# fmc_connector.net
KiCad netlist of a schematic drawn in Altium Designer
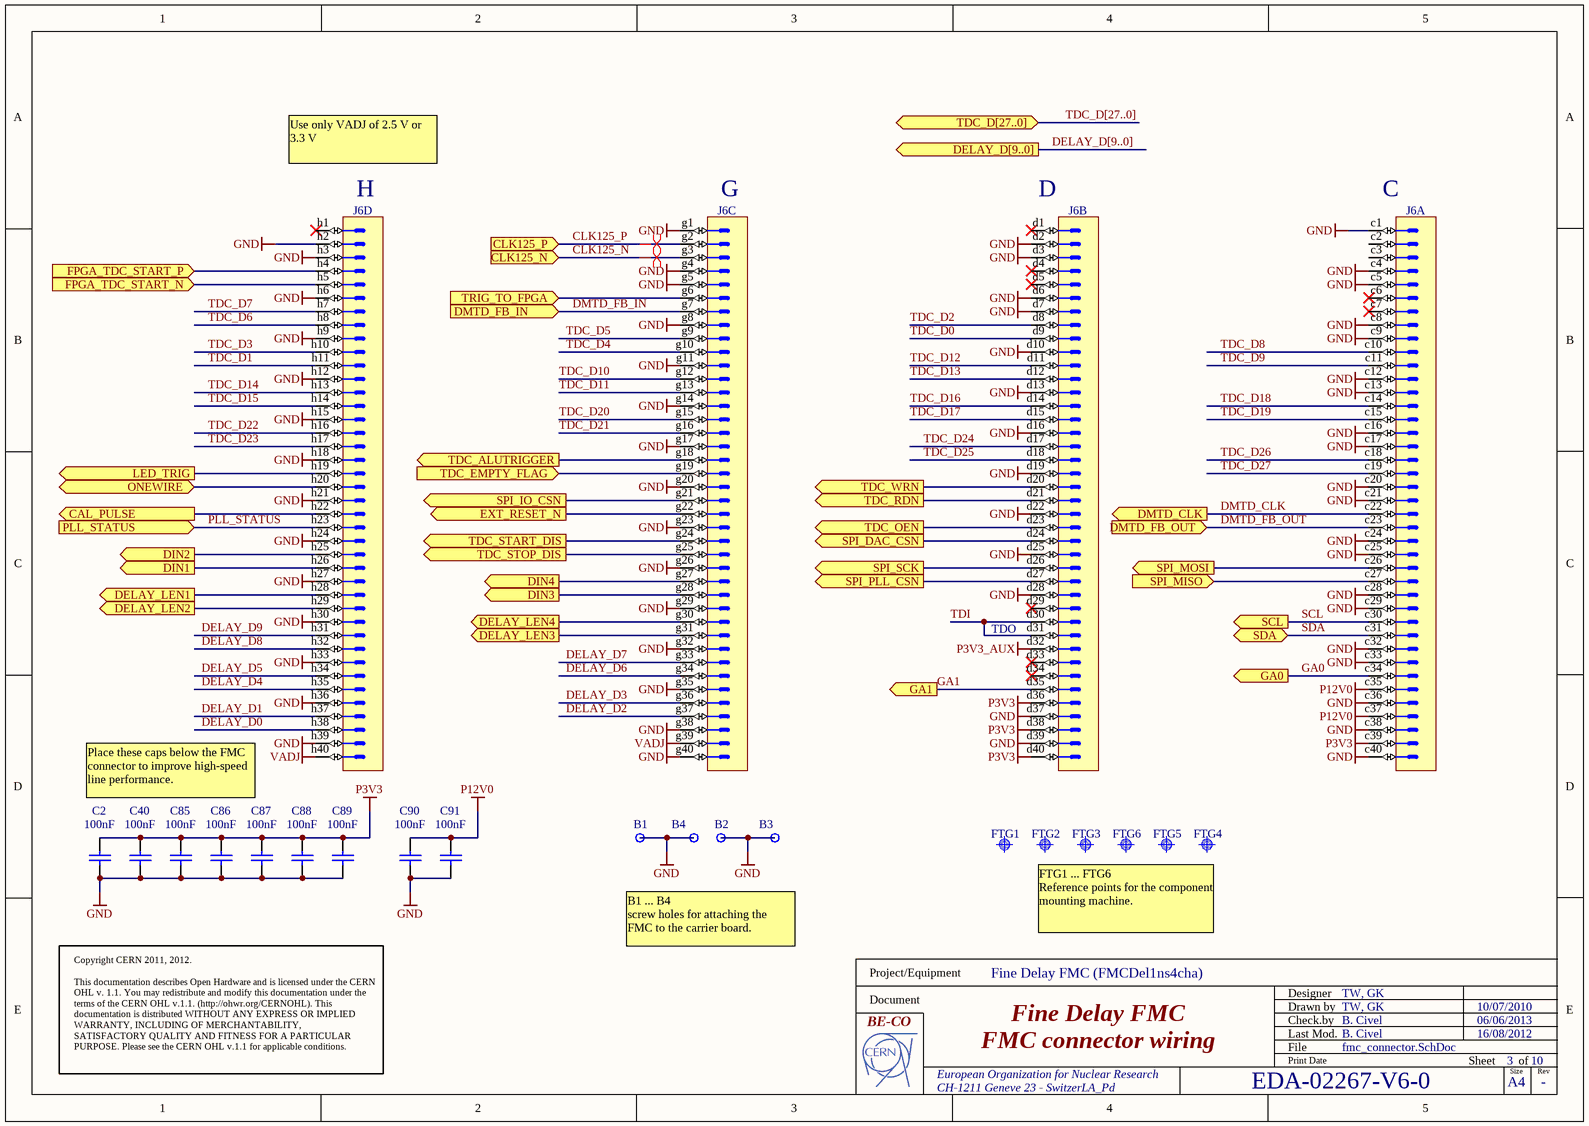
[diagram p0: fmc_connector.SchDoc]

(export (version "E")
  (design (tool "Eeschema 10.0.6"))
  (components
    (comp (ref "B1")
      (value "Plated Hole")
      (footprint "MTG300_600")
      (description "Single Terminal Socket")
      (fields (field (name "PART NUMBER") "PLATED_HOLE3.0_PAD6.0") (field (name "AUTHOR") "CERN DEM JLC"))
      (libsource (lib "Eletro-mechanical") (part "Single Terminal Socket"))
    )
    (comp (ref "B2")
      (value "Plated Hole")
      (footprint "MTG300_600")
      (description "Single Terminal Socket")
      (fields (field (name "PART NUMBER") "PLATED_HOLE3.0_PAD6.0") (field (name "AUTHOR") "CERN DEM JLC"))
      (libsource (lib "Eletro-mechanical") (part "Single Terminal Socket"))
    )
    (comp (ref "B3")
      (value "Plated Hole")
      (footprint "MTG300_600")
      (description "Single Terminal Socket")
      (fields (field (name "PART NUMBER") "PLATED_HOLE3.0_PAD6.0") (field (name "AUTHOR") "CERN DEM JLC"))
      (libsource (lib "Eletro-mechanical") (part "Single Terminal Socket"))
    )
    (comp (ref "B4")
      (value "Plated Hole")
      (footprint "MTG300_600")
      (description "Single Terminal Socket")
      (fields (field (name "PART NUMBER") "PLATED_HOLE3.0_PAD6.0") (field (name "AUTHOR") "CERN DEM JLC"))
      (libsource (lib "Eletro-mechanical") (part "Single Terminal Socket"))
    )
    (comp (ref "C2")
      (value "100nF")
      (footprint "CAPC1608X87N")
      (description "Non-polarised capacitor")
      (fields
        (field (name "PART NUMBER") "CC0603_100NF_50V_10%_X7R")
        (field (name "VOLTAGE") "50V")
        (field (name "AUTHOR") "CERN DEM JLC")
      )
      (libsource (lib "Capacitors") (part "Capacitor - non polarized"))
    )
    (comp (ref "C40")
      (value "100nF")
      (footprint "CAPC1608X87N")
      (description "Non-polarised capacitor")
      (fields
        (field (name "PART NUMBER") "CC0603_100NF_50V_10%_X7R")
        (field (name "VOLTAGE") "50V")
        (field (name "AUTHOR") "CERN DEM JLC")
      )
      (libsource (lib "Capacitors") (part "Capacitor - non polarized"))
    )
    (comp (ref "C85")
      (value "100nF")
      (footprint "CAPC1608X87N")
      (description "Non-polarised capacitor")
      (fields
        (field (name "PART NUMBER") "CC0603_100NF_50V_10%_X7R")
        (field (name "VOLTAGE") "50V")
        (field (name "AUTHOR") "CERN DEM JLC")
      )
      (libsource (lib "Capacitors") (part "Capacitor - non polarized"))
    )
    (comp (ref "C86")
      (value "100nF")
      (footprint "CAPC1608X87N")
      (description "Non-polarised capacitor")
      (fields
        (field (name "PART NUMBER") "CC0603_100NF_50V_10%_X7R")
        (field (name "VOLTAGE") "50V")
        (field (name "AUTHOR") "CERN DEM JLC")
      )
      (libsource (lib "Capacitors") (part "Capacitor - non polarized"))
    )
    (comp (ref "C87")
      (value "100nF")
      (footprint "CAPC1608X87N")
      (description "Non-polarised capacitor")
      (fields
        (field (name "PART NUMBER") "CC0603_100NF_50V_10%_X7R")
        (field (name "VOLTAGE") "50V")
        (field (name "AUTHOR") "CERN DEM JLC")
      )
      (libsource (lib "Capacitors") (part "Capacitor - non polarized"))
    )
    (comp (ref "C88")
      (value "100nF")
      (footprint "CAPC1608X87N")
      (description "Non-polarised capacitor")
      (fields
        (field (name "PART NUMBER") "CC0603_100NF_50V_10%_X7R")
        (field (name "VOLTAGE") "50V")
        (field (name "AUTHOR") "CERN DEM JLC")
      )
      (libsource (lib "Capacitors") (part "Capacitor - non polarized"))
    )
    (comp (ref "C89")
      (value "100nF")
      (footprint "CAPC1608X87N")
      (description "Non-polarised capacitor")
      (fields
        (field (name "PART NUMBER") "CC0603_100NF_50V_10%_X7R")
        (field (name "VOLTAGE") "50V")
        (field (name "AUTHOR") "CERN DEM JLC")
      )
      (libsource (lib "Capacitors") (part "Capacitor - non polarized"))
    )
    (comp (ref "C90")
      (value "100nF")
      (footprint "CAPC1608X87N")
      (description "Non-polarised capacitor")
      (fields
        (field (name "PART NUMBER") "CC0603_100NF_50V_10%_X7R")
        (field (name "VOLTAGE") "50V")
        (field (name "AUTHOR") "CERN DEM JLC")
      )
      (libsource (lib "Capacitors") (part "Capacitor - non polarized"))
    )
    (comp (ref "C91")
      (value "100nF")
      (footprint "CAPC1608X87N")
      (description "Non-polarised capacitor")
      (fields
        (field (name "PART NUMBER") "CC0603_100NF_50V_10%_X7R")
        (field (name "VOLTAGE") "50V")
        (field (name "AUTHOR") "CERN DEM JLC")
      )
      (libsource (lib "Capacitors") (part "Capacitor - non polarized"))
    )
    (comp (ref "FTG1")
      (value "Use only in PCB")
      (footprint "FIDUCIAL_TOP_S100-200")
      (description "Fiducial Target")
      (fields (field (name "PART NUMBER") "FIDUCIAL_TARGET_S100-200") (field (name "AUTHOR") "CERN DEM JLC"))
      (libsource (lib "Eletro-mechanical") (part "Fiducial Target"))
    )
    (comp (ref "FTG2")
      (value "Use only in PCB")
      (footprint "FIDUCIAL_TOP_S100-200")
      (description "Fiducial Target")
      (fields (field (name "PART NUMBER") "FIDUCIAL_TARGET_S100-200") (field (name "AUTHOR") "CERN DEM JLC"))
      (libsource (lib "Eletro-mechanical") (part "Fiducial Target"))
    )
    (comp (ref "FTG3")
      (value "Use only in PCB")
      (footprint "FIDUCIAL_TOP_S100-200")
      (description "Fiducial Target")
      (fields (field (name "PART NUMBER") "FIDUCIAL_TARGET_S100-200") (field (name "AUTHOR") "CERN DEM JLC"))
      (libsource (lib "Eletro-mechanical") (part "Fiducial Target"))
    )
    (comp (ref "FTG4")
      (value "Use only in PCB")
      (footprint "FIDUCIAL_TOP_S100-200")
      (description "Fiducial Target")
      (fields (field (name "PART NUMBER") "FIDUCIAL_TARGET_S100-200") (field (name "AUTHOR") "CERN DEM JLC"))
      (libsource (lib "Eletro-mechanical") (part "Fiducial Target"))
    )
    (comp (ref "FTG5")
      (value "Use only in PCB")
      (footprint "FIDUCIAL_TOP_S100-200")
      (description "Fiducial Target")
      (fields (field (name "PART NUMBER") "FIDUCIAL_TARGET_S100-200") (field (name "AUTHOR") "CERN DEM JLC"))
      (libsource (lib "Eletro-mechanical") (part "Fiducial Target"))
    )
    (comp (ref "FTG6")
      (value "Use only in PCB")
      (footprint "FIDUCIAL_TOP_S100-200")
      (description "Fiducial Target")
      (fields (field (name "PART NUMBER") "FIDUCIAL_TARGET_S100-200") (field (name "AUTHOR") "CERN DEM JLC"))
      (libsource (lib "Eletro-mechanical") (part "Fiducial Target"))
    )
    (comp (ref "J6")
      (value "VITA 57")
      (footprint "SAMTEC_ASP-134604-01")
      (description "Connector VITA 57, 160 Male contacts in 4 row cdgh")
      (fields
        (field (name "PART NUMBER") "SAMTEC_ASP-134604-01")
        (field (name "MANUFACTURER") "SAMTEC")
        (field (name "AUTHOR") "CERN DEM JLC")
      )
      (libsource (lib "Connectors") (part "Connector VITA 57 160 Male (cdgh)"))
    )
  )
  (nets
    (net (code "1") (name "/CAL_PULSE") (class "Default")
      (node (ref "J6") (pin "h22") (pinfunction "h22_h22") (pintype "bidirectional"))
    )
    (net (code "2") (name "/CLK125_N") (class "Default")
      (node (ref "J6") (pin "g3") (pinfunction "g3_g3") (pintype "bidirectional"))
    )
    (net (code "3") (name "/CLK125_P") (class "Default")
      (node (ref "J6") (pin "g2") (pinfunction "g2_g2") (pintype "bidirectional"))
    )
    (net (code "4") (name "/DELAY_D0") (class "Default")
      (node (ref "J6") (pin "h38") (pinfunction "h38_h38") (pintype "bidirectional"))
    )
    (net (code "5") (name "/DELAY_D1") (class "Default")
      (node (ref "J6") (pin "h37") (pinfunction "h37_h37") (pintype "bidirectional"))
    )
    (net (code "6") (name "/DELAY_D2") (class "Default")
      (node (ref "J6") (pin "g37") (pinfunction "g37_g37") (pintype "bidirectional"))
    )
    (net (code "7") (name "/DELAY_D3") (class "Default")
      (node (ref "J6") (pin "g36") (pinfunction "g36_g36") (pintype "bidirectional"))
    )
    (net (code "8") (name "/DELAY_D4") (class "Default")
      (node (ref "J6") (pin "h35") (pinfunction "h35_h35") (pintype "bidirectional"))
    )
    (net (code "9") (name "/DELAY_D5") (class "Default")
      (node (ref "J6") (pin "h34") (pinfunction "h34_h34") (pintype "bidirectional"))
    )
    (net (code "10") (name "/DELAY_D6") (class "Default")
      (node (ref "J6") (pin "g34") (pinfunction "g34_g34") (pintype "bidirectional"))
    )
    (net (code "11") (name "/DELAY_D7") (class "Default")
      (node (ref "J6") (pin "g33") (pinfunction "g33_g33") (pintype "bidirectional"))
    )
    (net (code "12") (name "/DELAY_D8") (class "Default")
      (node (ref "J6") (pin "h32") (pinfunction "h32_h32") (pintype "bidirectional"))
    )
    (net (code "13") (name "/DELAY_D9") (class "Default")
      (node (ref "J6") (pin "h31") (pinfunction "h31_h31") (pintype "bidirectional"))
    )
    (net (code "15") (name "/DELAY_LEN1") (class "Default")
      (node (ref "J6") (pin "h28") (pinfunction "h28_h28") (pintype "bidirectional"))
    )
    (net (code "16") (name "/DELAY_LEN2") (class "Default")
      (node (ref "J6") (pin "h29") (pinfunction "h29_h29") (pintype "bidirectional"))
    )
    (net (code "17") (name "/DELAY_LEN3") (class "Default")
      (node (ref "J6") (pin "g31") (pinfunction "g31_g31") (pintype "bidirectional"))
    )
    (net (code "18") (name "/DELAY_LEN4") (class "Default")
      (node (ref "J6") (pin "g30") (pinfunction "g30_g30") (pintype "bidirectional"))
    )
    (net (code "19") (name "/DIN1") (class "Default")
      (node (ref "J6") (pin "h26") (pinfunction "h26_h26") (pintype "bidirectional"))
    )
    (net (code "20") (name "/DIN2") (class "Default")
      (node (ref "J6") (pin "h25") (pinfunction "h25_h25") (pintype "bidirectional"))
    )
    (net (code "21") (name "/DIN3") (class "Default")
      (node (ref "J6") (pin "g28") (pinfunction "g28_g28") (pintype "bidirectional"))
    )
    (net (code "22") (name "/DIN4") (class "Default")
      (node (ref "J6") (pin "g27") (pinfunction "g27_g27") (pintype "bidirectional"))
    )
    (net (code "23") (name "/DMTD_CLK") (class "Default")
      (node (ref "J6") (pin "c22") (pinfunction "c22_c22") (pintype "bidirectional"))
    )
    (net (code "24") (name "/DMTD_FB_IN") (class "Default")
      (node (ref "J6") (pin "g7") (pinfunction "g7_g7") (pintype "bidirectional"))
    )
    (net (code "25") (name "/DMTD_FB_OUT") (class "Default")
      (node (ref "J6") (pin "c23") (pinfunction "c23_c23") (pintype "bidirectional"))
    )
    (net (code "26") (name "/EXT_RESET_N") (class "Default")
      (node (ref "J6") (pin "g22") (pinfunction "g22_g22") (pintype "bidirectional"))
    )
    (net (code "27") (name "/FPGA_TDC_START_N") (class "Default")
      (node (ref "J6") (pin "h5") (pinfunction "h5_h5") (pintype "bidirectional"))
    )
    (net (code "28") (name "/FPGA_TDC_START_P") (class "Default")
      (node (ref "J6") (pin "h4") (pinfunction "h4_h4") (pintype "bidirectional"))
    )
    (net (code "29") (name "/GA0") (class "Default")
      (node (ref "J6") (pin "c34") (pinfunction "c34_c34") (pintype "bidirectional"))
    )
    (net (code "30") (name "/GA1") (class "Default")
      (node (ref "J6") (pin "d35") (pinfunction "d35_d35") (pintype "bidirectional"))
    )
    (net (code "31") (name "/LED_TRIG") (class "Default")
      (node (ref "J6") (pin "h19") (pinfunction "h19_h19") (pintype "bidirectional"))
    )
    (net (code "32") (name "/ONEWIRE") (class "Default")
      (node (ref "J6") (pin "h20") (pinfunction "h20_h20") (pintype "bidirectional"))
    )
    (net (code "33") (name "/PLL_STATUS") (class "Default")
      (node (ref "J6") (pin "h23") (pinfunction "h23_h23") (pintype "bidirectional"))
    )
    (net (code "34") (name "/SCL") (class "Default")
      (node (ref "J6") (pin "c30") (pinfunction "c30_c30") (pintype "bidirectional"))
    )
    (net (code "35") (name "/SDA") (class "Default")
      (node (ref "J6") (pin "c31") (pinfunction "c31_c31") (pintype "bidirectional"))
    )
    (net (code "36") (name "/SPI_DAC_CSN") (class "Default")
      (node (ref "J6") (pin "d24") (pinfunction "d24_d24") (pintype "bidirectional"))
    )
    (net (code "37") (name "/SPI_IO_CSN") (class "Default")
      (node (ref "J6") (pin "g21") (pinfunction "g21_g21") (pintype "bidirectional"))
    )
    (net (code "38") (name "/SPI_MISO") (class "Default")
      (node (ref "J6") (pin "c27") (pinfunction "c27_c27") (pintype "bidirectional"))
    )
    (net (code "39") (name "/SPI_MOSI") (class "Default")
      (node (ref "J6") (pin "c26") (pinfunction "c26_c26") (pintype "bidirectional"))
    )
    (net (code "40") (name "/SPI_PLL_CSN") (class "Default")
      (node (ref "J6") (pin "d27") (pinfunction "d27_d27") (pintype "bidirectional"))
    )
    (net (code "41") (name "/SPI_SCK") (class "Default")
      (node (ref "J6") (pin "d26") (pinfunction "d26_d26") (pintype "bidirectional"))
    )
    (net (code "42") (name "/TDC_ALUTRIGGER") (class "Default")
      (node (ref "J6") (pin "g18") (pinfunction "g18_g18") (pintype "bidirectional"))
    )
    (net (code "43") (name "/TDC_D0") (class "Default")
      (node (ref "J6") (pin "d9") (pinfunction "d9_d9") (pintype "bidirectional"))
    )
    (net (code "44") (name "/TDC_D1") (class "Default")
      (node (ref "J6") (pin "h11") (pinfunction "h11_h11") (pintype "bidirectional"))
    )
    (net (code "45") (name "/TDC_D2") (class "Default")
      (node (ref "J6") (pin "d8") (pinfunction "d8_d8") (pintype "bidirectional"))
    )
    (net (code "46") (name "/TDC_D3") (class "Default")
      (node (ref "J6") (pin "h10") (pinfunction "h10_h10") (pintype "bidirectional"))
    )
    (net (code "47") (name "/TDC_D4") (class "Default")
      (node (ref "J6") (pin "g10") (pinfunction "g10_g10") (pintype "bidirectional"))
    )
    (net (code "48") (name "/TDC_D5") (class "Default")
      (node (ref "J6") (pin "g9") (pinfunction "g9_g9") (pintype "bidirectional"))
    )
    (net (code "49") (name "/TDC_D6") (class "Default")
      (node (ref "J6") (pin "h8") (pinfunction "h8_h8") (pintype "bidirectional"))
    )
    (net (code "50") (name "/TDC_D7") (class "Default")
      (node (ref "J6") (pin "h7") (pinfunction "h7_h7") (pintype "bidirectional"))
    )
    (net (code "51") (name "/TDC_D8") (class "Default")
      (node (ref "J6") (pin "c10") (pinfunction "c10_c10") (pintype "bidirectional"))
    )
    (net (code "52") (name "/TDC_D9") (class "Default")
      (node (ref "J6") (pin "c11") (pinfunction "c11_c11") (pintype "bidirectional"))
    )
    (net (code "53") (name "/TDC_D10") (class "Default")
      (node (ref "J6") (pin "g12") (pinfunction "g12_g12") (pintype "bidirectional"))
    )
    (net (code "54") (name "/TDC_D11") (class "Default")
      (node (ref "J6") (pin "g13") (pinfunction "g13_g13") (pintype "bidirectional"))
    )
    (net (code "55") (name "/TDC_D12") (class "Default")
      (node (ref "J6") (pin "d11") (pinfunction "d11_d11") (pintype "bidirectional"))
    )
    (net (code "56") (name "/TDC_D13") (class "Default")
      (node (ref "J6") (pin "d12") (pinfunction "d12_d12") (pintype "bidirectional"))
    )
    (net (code "57") (name "/TDC_D14") (class "Default")
      (node (ref "J6") (pin "h13") (pinfunction "h13_h13") (pintype "bidirectional"))
    )
    (net (code "58") (name "/TDC_D15") (class "Default")
      (node (ref "J6") (pin "h14") (pinfunction "h14_h14") (pintype "bidirectional"))
    )
    (net (code "59") (name "/TDC_D16") (class "Default")
      (node (ref "J6") (pin "d14") (pinfunction "d14_d14") (pintype "bidirectional"))
    )
    (net (code "60") (name "/TDC_D17") (class "Default")
      (node (ref "J6") (pin "d15") (pinfunction "d15_d15") (pintype "bidirectional"))
    )
    (net (code "61") (name "/TDC_D18") (class "Default")
      (node (ref "J6") (pin "c14") (pinfunction "c14_c14") (pintype "bidirectional"))
    )
    (net (code "62") (name "/TDC_D19") (class "Default")
      (node (ref "J6") (pin "c15") (pinfunction "c15_c15") (pintype "bidirectional"))
    )
    (net (code "63") (name "/TDC_D20") (class "Default")
      (node (ref "J6") (pin "g15") (pinfunction "g15_g15") (pintype "bidirectional"))
    )
    (net (code "64") (name "/TDC_D21") (class "Default")
      (node (ref "J6") (pin "g16") (pinfunction "g16_g16") (pintype "bidirectional"))
    )
    (net (code "65") (name "/TDC_D22") (class "Default")
      (node (ref "J6") (pin "h16") (pinfunction "h16_h16") (pintype "bidirectional"))
    )
    (net (code "66") (name "/TDC_D23") (class "Default")
      (node (ref "J6") (pin "h17") (pinfunction "h17_h17") (pintype "bidirectional"))
    )
    (net (code "67") (name "/TDC_D24") (class "Default")
      (node (ref "J6") (pin "d17") (pinfunction "d17_d17") (pintype "bidirectional"))
    )
    (net (code "68") (name "/TDC_D25") (class "Default")
      (node (ref "J6") (pin "d18") (pinfunction "d18_d18") (pintype "bidirectional"))
    )
    (net (code "69") (name "/TDC_D26") (class "Default")
      (node (ref "J6") (pin "c18") (pinfunction "c18_c18") (pintype "bidirectional"))
    )
    (net (code "70") (name "/TDC_D27") (class "Default")
      (node (ref "J6") (pin "c19") (pinfunction "c19_c19") (pintype "bidirectional"))
    )
    (net (code "72") (name "/TDC_EMPTY_FLAG") (class "Default")
      (node (ref "J6") (pin "g19") (pinfunction "g19_g19") (pintype "bidirectional"))
    )
    (net (code "73") (name "/TDC_OEN") (class "Default")
      (node (ref "J6") (pin "d23") (pinfunction "d23_d23") (pintype "bidirectional"))
    )
    (net (code "74") (name "/TDC_RDN") (class "Default")
      (node (ref "J6") (pin "d21") (pinfunction "d21_d21") (pintype "bidirectional"))
    )
    (net (code "75") (name "/TDC_START_DIS") (class "Default")
      (node (ref "J6") (pin "g24") (pinfunction "g24_g24") (pintype "bidirectional"))
    )
    (net (code "76") (name "/TDC_STOP_DIS") (class "Default")
      (node (ref "J6") (pin "g25") (pinfunction "g25_g25") (pintype "bidirectional"))
    )
    (net (code "77") (name "/TDC_WRN") (class "Default")
      (node (ref "J6") (pin "d20") (pinfunction "d20_d20") (pintype "bidirectional"))
    )
    (net (code "78") (name "/TDI") (class "Default")
      (node (ref "J6") (pin "d30") (pinfunction "d30_d30") (pintype "bidirectional"))
      (node (ref "J6") (pin "d31") (pinfunction "d31_d31") (pintype "bidirectional"))
    )
    (net (code "79") (name "/TRIG_TO_FPGA") (class "Default")
      (node (ref "J6") (pin "g6") (pinfunction "g6_g6") (pintype "bidirectional"))
    )
    (net (code "80") (name "GND") (class "Default")
      (node (ref "B1") (pin "1") (pinfunction "1_1") (pintype "bidirectional"))
      (node (ref "B2") (pin "1") (pinfunction "1_1") (pintype "bidirectional"))
      (node (ref "B3") (pin "1") (pinfunction "1_1") (pintype "bidirectional"))
      (node (ref "B4") (pin "1") (pinfunction "1_1") (pintype "bidirectional"))
      (node (ref "C2") (pin "1") (pinfunction "1_1") (pintype "passive"))
      (node (ref "C40") (pin "1") (pinfunction "1_1") (pintype "passive"))
      (node (ref "C85") (pin "1") (pinfunction "1_1") (pintype "passive"))
      (node (ref "C86") (pin "1") (pinfunction "1_1") (pintype "passive"))
      (node (ref "C87") (pin "1") (pinfunction "1_1") (pintype "passive"))
      (node (ref "C88") (pin "1") (pinfunction "1_1") (pintype "passive"))
      (node (ref "C89") (pin "1") (pinfunction "1_1") (pintype "passive"))
      (node (ref "C90") (pin "1") (pinfunction "1_1") (pintype "passive"))
      (node (ref "C91") (pin "1") (pinfunction "1_1") (pintype "passive"))
      (node (ref "J6") (pin "c1") (pinfunction "c1_c1") (pintype "bidirectional"))
      (node (ref "J6") (pin "c12") (pinfunction "c12_c12") (pintype "bidirectional"))
      (node (ref "J6") (pin "c13") (pinfunction "c13_c13") (pintype "bidirectional"))
      (node (ref "J6") (pin "c16") (pinfunction "c16_c16") (pintype "bidirectional"))
      (node (ref "J6") (pin "c17") (pinfunction "c17_c17") (pintype "bidirectional"))
      (node (ref "J6") (pin "c20") (pinfunction "c20_c20") (pintype "bidirectional"))
      (node (ref "J6") (pin "c21") (pinfunction "c21_c21") (pintype "bidirectional"))
      (node (ref "J6") (pin "c24") (pinfunction "c24_c24") (pintype "bidirectional"))
      (node (ref "J6") (pin "c25") (pinfunction "c25_c25") (pintype "bidirectional"))
      (node (ref "J6") (pin "c28") (pinfunction "c28_c28") (pintype "bidirectional"))
      (node (ref "J6") (pin "c29") (pinfunction "c29_c29") (pintype "bidirectional"))
      (node (ref "J6") (pin "c32") (pinfunction "c32_c32") (pintype "bidirectional"))
      (node (ref "J6") (pin "c33") (pinfunction "c33_c33") (pintype "bidirectional"))
      (node (ref "J6") (pin "c36") (pinfunction "c36_c36") (pintype "bidirectional"))
      (node (ref "J6") (pin "c38") (pinfunction "c38_c38") (pintype "bidirectional"))
      (node (ref "J6") (pin "c4") (pinfunction "c4_c4") (pintype "bidirectional"))
      (node (ref "J6") (pin "c40") (pinfunction "c40_c40") (pintype "bidirectional"))
      (node (ref "J6") (pin "c5") (pinfunction "c5_c5") (pintype "bidirectional"))
      (node (ref "J6") (pin "c8") (pinfunction "c8_c8") (pintype "bidirectional"))
      (node (ref "J6") (pin "c9") (pinfunction "c9_c9") (pintype "bidirectional"))
      (node (ref "J6") (pin "d10") (pinfunction "d10_d10") (pintype "bidirectional"))
      (node (ref "J6") (pin "d13") (pinfunction "d13_d13") (pintype "bidirectional"))
      (node (ref "J6") (pin "d16") (pinfunction "d16_d16") (pintype "bidirectional"))
      (node (ref "J6") (pin "d19") (pinfunction "d19_d19") (pintype "bidirectional"))
      (node (ref "J6") (pin "d2") (pinfunction "d2_d2") (pintype "bidirectional"))
      (node (ref "J6") (pin "d22") (pinfunction "d22_d22") (pintype "bidirectional"))
      (node (ref "J6") (pin "d25") (pinfunction "d25_d25") (pintype "bidirectional"))
      (node (ref "J6") (pin "d28") (pinfunction "d28_d28") (pintype "bidirectional"))
      (node (ref "J6") (pin "d3") (pinfunction "d3_d3") (pintype "bidirectional"))
      (node (ref "J6") (pin "d37") (pinfunction "d37_d37") (pintype "bidirectional"))
      (node (ref "J6") (pin "d39") (pinfunction "d39_d39") (pintype "bidirectional"))
      (node (ref "J6") (pin "d6") (pinfunction "d6_d6") (pintype "bidirectional"))
      (node (ref "J6") (pin "d7") (pinfunction "d7_d7") (pintype "bidirectional"))
      (node (ref "J6") (pin "g1") (pinfunction "g1_g1") (pintype "bidirectional"))
      (node (ref "J6") (pin "g11") (pinfunction "g11_g11") (pintype "bidirectional"))
      (node (ref "J6") (pin "g14") (pinfunction "g14_g14") (pintype "bidirectional"))
      (node (ref "J6") (pin "g17") (pinfunction "g17_g17") (pintype "bidirectional"))
      (node (ref "J6") (pin "g20") (pinfunction "g20_g20") (pintype "bidirectional"))
      (node (ref "J6") (pin "g23") (pinfunction "g23_g23") (pintype "bidirectional"))
      (node (ref "J6") (pin "g26") (pinfunction "g26_g26") (pintype "bidirectional"))
      (node (ref "J6") (pin "g29") (pinfunction "g29_g29") (pintype "bidirectional"))
      (node (ref "J6") (pin "g32") (pinfunction "g32_g32") (pintype "bidirectional"))
      (node (ref "J6") (pin "g35") (pinfunction "g35_g35") (pintype "bidirectional"))
      (node (ref "J6") (pin "g38") (pinfunction "g38_g38") (pintype "bidirectional"))
      (node (ref "J6") (pin "g4") (pinfunction "g4_g4") (pintype "bidirectional"))
      (node (ref "J6") (pin "g40") (pinfunction "g40_g40") (pintype "bidirectional"))
      (node (ref "J6") (pin "g5") (pinfunction "g5_g5") (pintype "bidirectional"))
      (node (ref "J6") (pin "g8") (pinfunction "g8_g8") (pintype "bidirectional"))
      (node (ref "J6") (pin "h12") (pinfunction "h12_h12") (pintype "bidirectional"))
      (node (ref "J6") (pin "h15") (pinfunction "h15_h15") (pintype "bidirectional"))
      (node (ref "J6") (pin "h18") (pinfunction "h18_h18") (pintype "bidirectional"))
      (node (ref "J6") (pin "h2") (pinfunction "h2_h2") (pintype "bidirectional"))
      (node (ref "J6") (pin "h21") (pinfunction "h21_h21") (pintype "bidirectional"))
      (node (ref "J6") (pin "h24") (pinfunction "h24_h24") (pintype "bidirectional"))
      (node (ref "J6") (pin "h27") (pinfunction "h27_h27") (pintype "bidirectional"))
      (node (ref "J6") (pin "h3") (pinfunction "h3_h3") (pintype "bidirectional"))
      (node (ref "J6") (pin "h30") (pinfunction "h30_h30") (pintype "bidirectional"))
      (node (ref "J6") (pin "h33") (pinfunction "h33_h33") (pintype "bidirectional"))
      (node (ref "J6") (pin "h36") (pinfunction "h36_h36") (pintype "bidirectional"))
      (node (ref "J6") (pin "h39") (pinfunction "h39_h39") (pintype "bidirectional"))
      (node (ref "J6") (pin "h6") (pinfunction "h6_h6") (pintype "bidirectional"))
      (node (ref "J6") (pin "h9") (pinfunction "h9_h9") (pintype "bidirectional"))
    )
    (net (code "81") (name "P3V3") (class "Default")
      (node (ref "C2") (pin "2") (pinfunction "2_2") (pintype "passive"))
      (node (ref "C40") (pin "2") (pinfunction "2_2") (pintype "passive"))
      (node (ref "C85") (pin "2") (pinfunction "2_2") (pintype "passive"))
      (node (ref "C86") (pin "2") (pinfunction "2_2") (pintype "passive"))
      (node (ref "C87") (pin "2") (pinfunction "2_2") (pintype "passive"))
      (node (ref "C88") (pin "2") (pinfunction "2_2") (pintype "passive"))
      (node (ref "C89") (pin "2") (pinfunction "2_2") (pintype "passive"))
      (node (ref "J6") (pin "c39") (pinfunction "c39_c39") (pintype "bidirectional"))
      (node (ref "J6") (pin "d36") (pinfunction "d36_d36") (pintype "bidirectional"))
      (node (ref "J6") (pin "d38") (pinfunction "d38_d38") (pintype "bidirectional"))
      (node (ref "J6") (pin "d40") (pinfunction "d40_d40") (pintype "bidirectional"))
    )
    (net (code "82") (name "P3V3_AUX") (class "Default")
      (node (ref "J6") (pin "d32") (pinfunction "d32_d32") (pintype "bidirectional"))
    )
    (net (code "83") (name "P12V0") (class "Default")
      (node (ref "C90") (pin "2") (pinfunction "2_2") (pintype "passive"))
      (node (ref "C91") (pin "2") (pinfunction "2_2") (pintype "passive"))
      (node (ref "J6") (pin "c35") (pinfunction "c35_c35") (pintype "bidirectional"))
      (node (ref "J6") (pin "c37") (pinfunction "c37_c37") (pintype "bidirectional"))
    )
    (net (code "84") (name "VADJ") (class "Default")
      (node (ref "J6") (pin "g39") (pinfunction "g39_g39") (pintype "bidirectional"))
      (node (ref "J6") (pin "h40") (pinfunction "h40_h40") (pintype "bidirectional"))
    )
    (net (code "85") (name "unconnected-(J6-Padc2)") (class "Default")
      (node (ref "J6") (pin "c2") (pinfunction "c2_c2") (pintype "bidirectional"))
    )
    (net (code "86") (name "unconnected-(J6-Padc3)") (class "Default")
      (node (ref "J6") (pin "c3") (pinfunction "c3_c3") (pintype "bidirectional"))
    )
    (net (code "87") (name "unconnected-(J6-Padc6)") (class "Default")
      (node (ref "J6") (pin "c6") (pinfunction "c6_c6") (pintype "bidirectional+no_connect"))
    )
    (net (code "88") (name "unconnected-(J6-Padc7)") (class "Default")
      (node (ref "J6") (pin "c7") (pinfunction "c7_c7") (pintype "bidirectional+no_connect"))
    )
    (net (code "89") (name "unconnected-(J6-Padd1)") (class "Default")
      (node (ref "J6") (pin "d1") (pinfunction "d1_d1") (pintype "bidirectional+no_connect"))
    )
    (net (code "90") (name "unconnected-(J6-Padd4)") (class "Default")
      (node (ref "J6") (pin "d4") (pinfunction "d4_d4") (pintype "bidirectional+no_connect"))
    )
    (net (code "91") (name "unconnected-(J6-Padd5)") (class "Default")
      (node (ref "J6") (pin "d5") (pinfunction "d5_d5") (pintype "bidirectional+no_connect"))
    )
    (net (code "92") (name "unconnected-(J6-Padd29)") (class "Default")
      (node (ref "J6") (pin "d29") (pinfunction "d29_d29") (pintype "bidirectional+no_connect"))
    )
    (net (code "93") (name "unconnected-(J6-Padd33)") (class "Default")
      (node (ref "J6") (pin "d33") (pinfunction "d33_d33") (pintype "bidirectional+no_connect"))
    )
    (net (code "94") (name "unconnected-(J6-Padd34)") (class "Default")
      (node (ref "J6") (pin "d34") (pinfunction "d34_d34") (pintype "bidirectional+no_connect"))
    )
    (net (code "95") (name "unconnected-(J6-Padh1)") (class "Default")
      (node (ref "J6") (pin "h1") (pinfunction "h1_h1") (pintype "bidirectional+no_connect"))
    )
  )
)
